# lanternLED.net
KiCad netlist of a schematic drawn in EAGLE
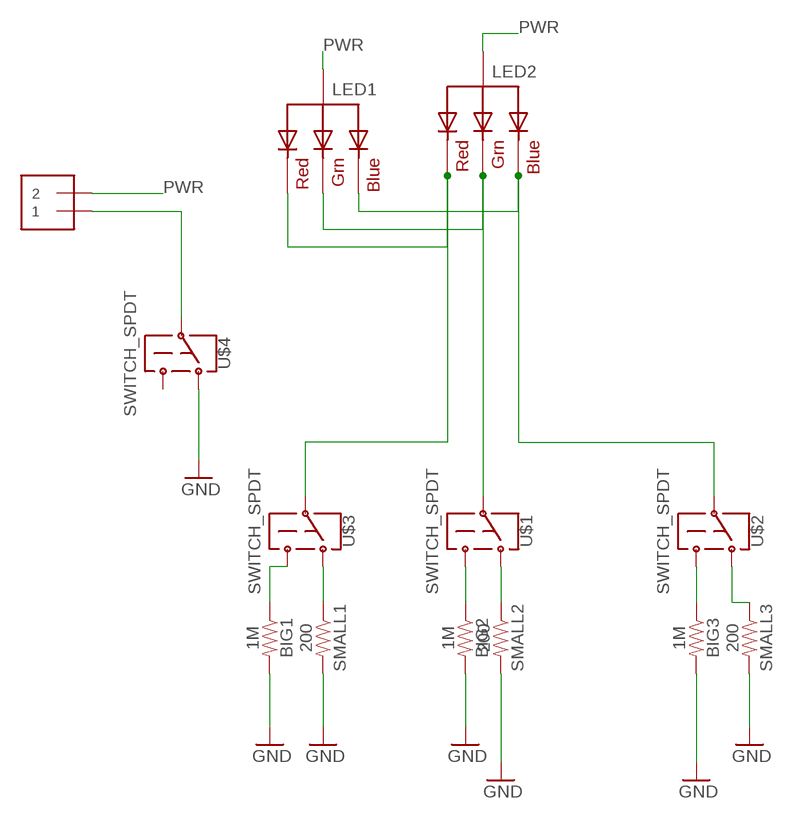
[diagram p0: schematic, sheet 1]

(export (version "E")
  (design (tool "Eeschema 10.0.6"))
  (components
    (comp (ref "BIG1")
      (value "1M")
      (footprint "eagle-import:0603")
      (libsource (lib "eagle-import") (part "10KOHM-0603-1/10W-1%"))
    )
    (comp (ref "BIG2")
      (value "1M")
      (footprint "eagle-import:0603")
      (libsource (lib "eagle-import") (part "10KOHM-0603-1/10W-1%"))
    )
    (comp (ref "BIG3")
      (value "1M")
      (footprint "eagle-import:0603")
      (libsource (lib "eagle-import") (part "10KOHM-0603-1/10W-1%"))
    )
    (comp (ref "J1")
      (value "1X2BIGGERHOLES")
      (footprint "eagle-import:1X2-4.5MM")
      (libsource (lib "eagle-import") (part "1X2BIGGERHOLES"))
    )
    (comp (ref "LED1")
      (value "RGBLED_CA-PIRANHA")
      (footprint "eagle-import:PIRANHA5MM")
      (libsource (lib "eagle-import") (part "RGBLED_CA-PIRANHA"))
    )
    (comp (ref "LED2")
      (value "RGBLED_CA-PIRANHA")
      (footprint "eagle-import:PIRANHA5MM")
      (libsource (lib "eagle-import") (part "RGBLED_CA-PIRANHA"))
    )
    (comp (ref "SMALL1")
      (value "200")
      (footprint "eagle-import:0603")
      (libsource (lib "eagle-import") (part "4.7KOHM-0603-1/10W-1%"))
    )
    (comp (ref "SMALL2")
      (value "200")
      (footprint "eagle-import:0603")
      (libsource (lib "eagle-import") (part "4.7KOHM-0603-1/10W-1%"))
    )
    (comp (ref "SMALL3")
      (value "200")
      (footprint "eagle-import:0603")
      (libsource (lib "eagle-import") (part "4.7KOHM-0603-1/10W-1%"))
    )
    (comp (ref "U$1")
      (value "SWITCH_SPDT")
      (footprint "eagle-import:SWITCH_SPDT_SMD_CLSB12B")
      (libsource (lib "eagle-import") (part "SWITCH_SPDT"))
    )
    (comp (ref "U$2")
      (value "SWITCH_SPDT")
      (footprint "eagle-import:SWITCH_SPDT_SMD_CLSB12B")
      (libsource (lib "eagle-import") (part "SWITCH_SPDT"))
    )
    (comp (ref "U$3")
      (value "SWITCH_SPDT")
      (footprint "eagle-import:SWITCH_SPDT_SMD_CLSB12B")
      (libsource (lib "eagle-import") (part "SWITCH_SPDT"))
    )
    (comp (ref "U$4")
      (value "SWITCH_SPDT")
      (footprint "eagle-import:SWITCH_SPDT_SMD_CLSB12B")
      (libsource (lib "eagle-import") (part "SWITCH_SPDT"))
    )
  )
  (nets
    (net (code "1") (name "/PWR") (class "Default")
      (node (ref "J1") (pin "2") (pinfunction "2_2") (pintype "passive"))
      (node (ref "LED1") (pin "4") (pinfunction "VCC_4") (pintype "bidirectional"))
      (node (ref "LED2") (pin "4") (pinfunction "VCC_4") (pintype "bidirectional"))
    )
    (net (code "2") (name "GND") (class "Default")
      (node (ref "BIG1") (pin "2") (pinfunction "2_2") (pintype "passive"))
      (node (ref "BIG2") (pin "2") (pinfunction "2_2") (pintype "passive"))
      (node (ref "BIG3") (pin "2") (pinfunction "2_2") (pintype "passive"))
      (node (ref "SMALL1") (pin "2") (pinfunction "2_2") (pintype "passive"))
      (node (ref "SMALL2") (pin "2") (pinfunction "2_2") (pintype "passive"))
      (node (ref "SMALL3") (pin "2") (pinfunction "2_2") (pintype "passive"))
      (node (ref "U$4") (pin "SIDER") (pinfunction "SIDER_SIDER") (pintype "bidirectional"))
    )
    (net (code "3") (name "Net-(BIG1-Pad1)") (class "Default")
      (node (ref "BIG1") (pin "1") (pinfunction "1_1") (pintype "passive"))
      (node (ref "U$3") (pin "SIDEL") (pinfunction "SIDEL_SIDEL") (pintype "bidirectional"))
    )
    (net (code "4") (name "Net-(BIG2-Pad1)") (class "Default")
      (node (ref "BIG2") (pin "1") (pinfunction "1_1") (pintype "passive"))
      (node (ref "U$1") (pin "SIDEL") (pinfunction "SIDEL_SIDEL") (pintype "bidirectional"))
    )
    (net (code "5") (name "Net-(BIG3-Pad1)") (class "Default")
      (node (ref "BIG3") (pin "1") (pinfunction "1_1") (pintype "passive"))
      (node (ref "U$2") (pin "SIDEL") (pinfunction "SIDEL_SIDEL") (pintype "bidirectional"))
    )
    (net (code "6") (name "Net-(LED1-BLUE)") (class "Default")
      (node (ref "LED1") (pin "1") (pinfunction "BLUE_1") (pintype "bidirectional"))
      (node (ref "LED2") (pin "1") (pinfunction "BLUE_1") (pintype "bidirectional"))
      (node (ref "U$2") (pin "TOP") (pinfunction "SINGLE_TOP") (pintype "bidirectional"))
    )
    (net (code "7") (name "Net-(LED1-GREEN)") (class "Default")
      (node (ref "LED1") (pin "3") (pinfunction "GREEN_3") (pintype "bidirectional"))
      (node (ref "LED2") (pin "3") (pinfunction "GREEN_3") (pintype "bidirectional"))
      (node (ref "U$1") (pin "TOP") (pinfunction "SINGLE_TOP") (pintype "bidirectional"))
    )
    (net (code "8") (name "Net-(LED1-RED)") (class "Default")
      (node (ref "LED1") (pin "2") (pinfunction "RED_2") (pintype "bidirectional"))
      (node (ref "LED2") (pin "2") (pinfunction "RED_2") (pintype "bidirectional"))
      (node (ref "U$3") (pin "TOP") (pinfunction "SINGLE_TOP") (pintype "bidirectional"))
    )
    (net (code "9") (name "Net-(SMALL1-Pad1)") (class "Default")
      (node (ref "SMALL1") (pin "1") (pinfunction "1_1") (pintype "passive"))
      (node (ref "U$3") (pin "SIDER") (pinfunction "SIDER_SIDER") (pintype "bidirectional"))
    )
    (net (code "10") (name "Net-(SMALL2-Pad1)") (class "Default")
      (node (ref "SMALL2") (pin "1") (pinfunction "1_1") (pintype "passive"))
      (node (ref "U$1") (pin "SIDER") (pinfunction "SIDER_SIDER") (pintype "bidirectional"))
    )
    (net (code "11") (name "Net-(SMALL3-Pad1)") (class "Default")
      (node (ref "SMALL3") (pin "1") (pinfunction "1_1") (pintype "passive"))
      (node (ref "U$2") (pin "SIDER") (pinfunction "SIDER_SIDER") (pintype "bidirectional"))
    )
    (net (code "12") (name "Net-(U$4-SINGLE)") (class "Default")
      (node (ref "J1") (pin "1") (pinfunction "1_1") (pintype "passive"))
      (node (ref "U$4") (pin "TOP") (pinfunction "SINGLE_TOP") (pintype "bidirectional"))
    )
    (net (code "13") (name "unconnected-(U$4-PadSIDEL)") (class "Default")
      (node (ref "U$4") (pin "SIDEL") (pinfunction "SIDEL_SIDEL") (pintype "bidirectional"))
    )
  )
)
